# Sheet-NODE-V1_0.net
KiCad netlist of a schematic drawn in Altium Designer
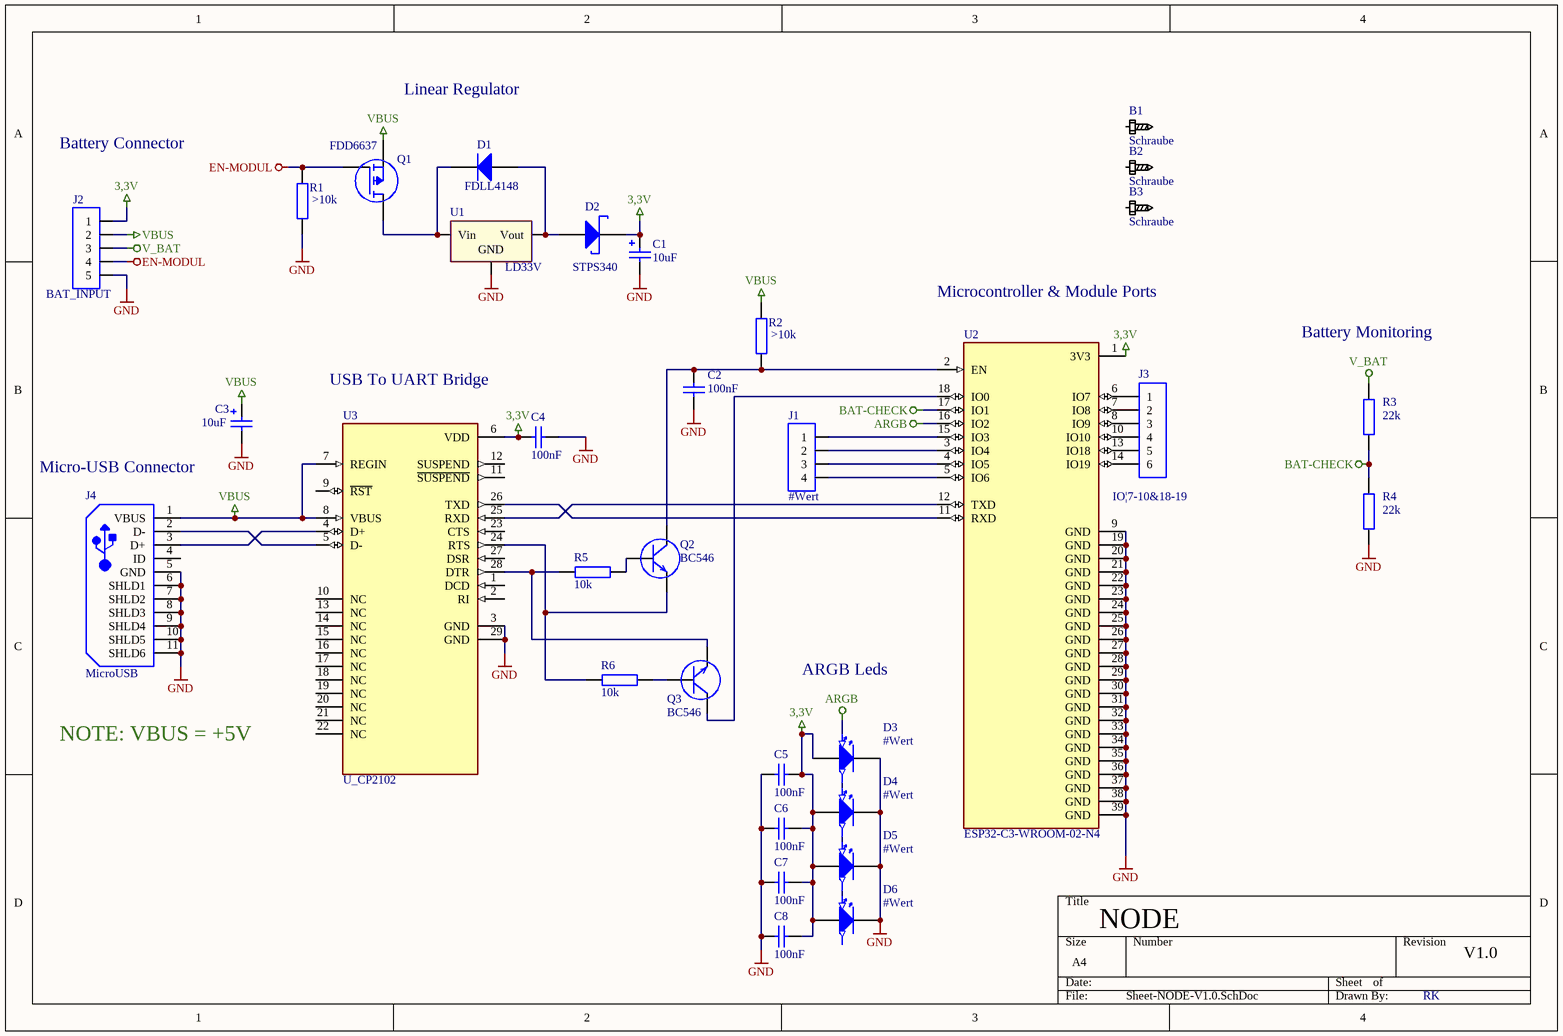
[diagram p0: Sheet-NODE-V1.0.SchDoc]

(export (version "E")
  (design (tool "Eeschema 10.0.6"))
  (components
    (comp (ref "B1")
      (value "Schraube")
      (footprint "B_Schraube-M3 PAD")
      (description "Schraubenloch für M3 Schrauben")
      (libsource (lib "SCHLIB-PCSB_5.1.3") (part "B_Schraube"))
    )
    (comp (ref "B2")
      (value "Schraube")
      (footprint "B_Schraube-M3 PAD")
      (description "Schraubenloch für M3 Schrauben")
      (libsource (lib "SCHLIB-PCSB_5.1.3") (part "B_Schraube"))
    )
    (comp (ref "B3")
      (value "Schraube")
      (footprint "B_Schraube-M3 PAD")
      (description "Schraubenloch für M3 Schrauben")
      (libsource (lib "SCHLIB-PCSB_5.1.3") (part "B_Schraube"))
    )
    (comp (ref "C1")
      (value "10uF")
      (footprint "C_SMD_B-Typ")
      (description "SMD Elektrolytkondensator")
      (libsource (lib "SCHLIB-PCSB_5.1.3") (part "C_SMD_ELK"))
    )
    (comp (ref "C2")
      (value "100nF")
      (footprint "C_SMD_0603")
      (description "Kondensator SMD Universal, Keramik, Folie, usw.")
      (libsource (lib "SCHLIB-PCSB_5.1.3") (part "C_SMD_KO"))
    )
    (comp (ref "C3")
      (value "10uF")
      (footprint "C_SMD_B-Typ")
      (description "SMD Elektrolytkondensator")
      (libsource (lib "SCHLIB-PCSB_5.1.3") (part "C_SMD_ELK"))
    )
    (comp (ref "C4")
      (value "100nF")
      (footprint "C_SMD_0603")
      (description "Kondensator SMD Universal, Keramik, Folie, usw.")
      (libsource (lib "SCHLIB-PCSB_5.1.3") (part "C_SMD_KO"))
    )
    (comp (ref "C5")
      (value "100nF")
      (footprint "C_SMD_0603")
      (description "Kondensator SMD Universal, Keramik, Folie, usw.")
      (libsource (lib "SCHLIB-PCSB_5.1.3") (part "C_SMD_KO"))
    )
    (comp (ref "C6")
      (value "100nF")
      (footprint "C_SMD_0603")
      (description "Kondensator SMD Universal, Keramik, Folie, usw.")
      (libsource (lib "SCHLIB-PCSB_5.1.3") (part "C_SMD_KO"))
    )
    (comp (ref "C7")
      (value "100nF")
      (footprint "C_SMD_0603")
      (description "Kondensator SMD Universal, Keramik, Folie, usw.")
      (libsource (lib "SCHLIB-PCSB_5.1.3") (part "C_SMD_KO"))
    )
    (comp (ref "C8")
      (value "100nF")
      (footprint "C_SMD_0603")
      (description "Kondensator SMD Universal, Keramik, Folie, usw.")
      (libsource (lib "SCHLIB-PCSB_5.1.3") (part "C_SMD_KO"))
    )
    (comp (ref "D1")
      (value "FDLL4148")
      (footprint "SOD-80-2")
      (description "Diode SMD Silizium")
      (libsource (lib "SCHLIB-PCSB_5.1.3") (part "D_SMD_Silizium"))
    )
    (comp (ref "D2")
      (value "STPS340")
      (footprint "D_DO-214")
      (description "Diode SMD Schottky")
      (libsource (lib "SCHLIB-PCSB_5.1.3") (part "D_SMD_Schottky"))
    )
    (comp (ref "D3")
      (value "#Wert")
      (footprint "D_SMD_LED-ARGB")
      (description "Diode SMD ARGB")
      (libsource (lib "SCHLIB-PCSB_5.1.3") (part "D_SMD_LED-ARGB"))
    )
    (comp (ref "D4")
      (value "#Wert")
      (footprint "D_SMD_LED-ARGB")
      (description "Diode SMD ARGB")
      (libsource (lib "SCHLIB-PCSB_5.1.3") (part "D_SMD_LED-ARGB"))
    )
    (comp (ref "D5")
      (value "#Wert")
      (footprint "D_SMD_LED-ARGB")
      (description "Diode SMD ARGB")
      (libsource (lib "SCHLIB-PCSB_5.1.3") (part "D_SMD_LED-ARGB"))
    )
    (comp (ref "D6")
      (value "#Wert")
      (footprint "D_SMD_LED-ARGB")
      (description "Diode SMD ARGB")
      (libsource (lib "SCHLIB-PCSB_5.1.3") (part "D_SMD_LED-ARGB"))
    )
    (comp (ref "J1")
      (value "#Wert")
      (footprint "Sip-4")
      (description "Stecker")
      (libsource (lib "SCHLIB-PCSB_5.1.3") (part "J_THT_CON4"))
    )
    (comp (ref "J2")
      (value "BAT_INPUT")
      (footprint "SIP-5")
      (description "Stecker")
      (libsource (lib "SCHLIB-PCSB_5.1.3") (part "J_THT_CON5"))
    )
    (comp (ref "J3")
      (value "IO¦7-10&18-19")
      (footprint "SIP-6")
      (description "Stecker")
      (libsource (lib "SCHLIB-PCSB_5.1.3") (part "J_THT_CON6"))
    )
    (comp (ref "J4")
      (value "MicroUSB")
      (footprint "J-SMD-Micro-USB")
      (description "Micro USB Buchse")
      (libsource (lib "SCHLIB-PCSB_5.1.3") (part "J_SMD_µ-USB"))
    )
    (comp (ref "Q1")
      (value "FDD6637")
      (footprint "FDD6637_TO-252-3")
      (description "P-Kanal MOSFET")
      (fields (field (name "MP") "IRFZ44NPBF") (field (name "DIGI-KEY_PART_NUMBER") "IRFZ44NPBF-ND"))
      (libsource (lib "SCHLIB-PCSB_5.1.3") (part "Q_SMD_MOSFET-P-Kanal"))
    )
    (comp (ref "Q2")
      (value "BC546")
      (footprint "TO-92-3")
      (description "NPN Transistor")
      (libsource (lib "SCHLIB-PCSB_5.1.3") (part "Q_SMD_NPN"))
    )
    (comp (ref "Q3")
      (value "BC546")
      (footprint "TO-92-3")
      (description "NPN Transistor")
      (libsource (lib "SCHLIB-PCSB_5.1.3") (part "Q_SMD_NPN"))
    )
    (comp (ref "R1")
      (value ">10k")
      (footprint "R_SMD_0805")
      (description "Widerstand SMD")
      (libsource (lib "SCHLIB-PCSB_5.1.3") (part "R_SMD_Widerstand"))
    )
    (comp (ref "R2")
      (value ">10k")
      (footprint "R_SMD_0805")
      (description "Widerstand SMD")
      (libsource (lib "SCHLIB-PCSB_5.1.3") (part "R_SMD_Widerstand"))
    )
    (comp (ref "R3")
      (value "22k")
      (footprint "R_SMD_0805")
      (description "Widerstand SMD")
      (libsource (lib "SCHLIB-PCSB_5.1.3") (part "R_SMD_Widerstand"))
    )
    (comp (ref "R4")
      (value "22k")
      (footprint "R_SMD_0805")
      (description "Widerstand SMD")
      (libsource (lib "SCHLIB-PCSB_5.1.3") (part "R_SMD_Widerstand"))
    )
    (comp (ref "R5")
      (value "10k")
      (footprint "R_SMD_0805")
      (description "Widerstand SMD")
      (libsource (lib "SCHLIB-PCSB_5.1.3") (part "R_SMD_Widerstand"))
    )
    (comp (ref "R6")
      (value "10k")
      (footprint "R_SMD_0805")
      (description "Widerstand SMD")
      (libsource (lib "SCHLIB-PCSB_5.1.3") (part "R_SMD_Widerstand"))
    )
    (comp (ref "U1")
      (value "LD33V")
      (footprint "TO-220-3V")
      (description "Linearwandler")
      (libsource (lib "SCHLIB-PCSB_5.1.3") (part "U_THT_78xx"))
    )
    (comp (ref "U2")
      (value "ESP32-C3-WROOM-02-N4")
      (footprint "MODULE_ESP32-C3-WROOM-02-H4")
      (fields (field (name "MF") "Espressif Systems"))
      (libsource (lib "SCHLIB-PCSB_5.1.3") (part "ESP32-C3-WROOM-02-N4"))
    )
    (comp (ref "U3")
      (value "U_CP2102")
      (footprint "QFN50P500X500X100-29N")
      (description "CP2102N USB 2.0 to UART (RS232) Bridge Interface Evaluation Board")
      (fields (field (name "MF") "Silicon Labs") (field (name "MP") "CP2102"))
      (libsource (lib "SCHLIB-PCSB_5.1.3") (part "U_CP2102"))
    )
  )
  (nets
    (net (code "1") (name "3,3V") (class "Default")
      (node (ref "C1") (pin "1") (pinfunction "1_1") (pintype "passive"))
      (node (ref "C4") (pin "1") (pintype "passive"))
      (node (ref "C5") (pin "2") (pintype "passive"))
      (node (ref "C6") (pin "2") (pintype "passive"))
      (node (ref "C7") (pin "2") (pintype "passive"))
      (node (ref "C8") (pin "2") (pintype "passive"))
      (node (ref "D2") (pin "2") (pinfunction "K_2") (pintype "passive"))
      (node (ref "D3") (pin "1") (pinfunction "VDD_1") (pintype "passive"))
      (node (ref "D4") (pin "1") (pinfunction "VDD_1") (pintype "passive"))
      (node (ref "D5") (pin "1") (pinfunction "VDD_1") (pintype "passive"))
      (node (ref "D6") (pin "1") (pinfunction "VDD_1") (pintype "passive"))
      (node (ref "J2") (pin "1") (pinfunction "1_1") (pintype "passive"))
      (node (ref "U2") (pin "1") (pinfunction "3V3_1") (pintype "power_in"))
      (node (ref "U3") (pin "6") (pinfunction "VDD_6") (pintype "power_in"))
    )
    (net (code "2") (name "ARGB") (class "Default")
      (node (ref "D3") (pin "4") (pinfunction "DIN_4") (pintype "input"))
      (node (ref "U2") (pin "16") (pinfunction "IO2_16") (pintype "bidirectional"))
    )
    (net (code "3") (name "BAT-CHECK") (class "Default")
      (node (ref "R3") (pin "1") (pintype "passive"))
      (node (ref "R4") (pin "2") (pintype "passive"))
      (node (ref "U2") (pin "17") (pinfunction "IO1_17") (pintype "bidirectional"))
    )
    (net (code "4") (name "EN-MODUL") (class "Default")
      (node (ref "J2") (pin "4") (pinfunction "4_4") (pintype "passive"))
      (node (ref "Q1") (pin "G") (pinfunction "G_G") (pintype "passive"))
      (node (ref "R1") (pin "2") (pintype "passive"))
    )
    (net (code "5") (name "GND") (class "Default")
      (node (ref "C1") (pin "2") (pinfunction "2_2") (pintype "passive"))
      (node (ref "C2") (pin "1") (pintype "passive"))
      (node (ref "C3") (pin "2") (pinfunction "2_2") (pintype "passive"))
      (node (ref "C4") (pin "2") (pintype "passive"))
      (node (ref "C5") (pin "1") (pintype "passive"))
      (node (ref "C6") (pin "1") (pintype "passive"))
      (node (ref "C7") (pin "1") (pintype "passive"))
      (node (ref "C8") (pin "1") (pintype "passive"))
      (node (ref "D3") (pin "3") (pinfunction "GND_3") (pintype "passive"))
      (node (ref "D4") (pin "3") (pinfunction "GND_3") (pintype "passive"))
      (node (ref "D5") (pin "3") (pinfunction "GND_3") (pintype "passive"))
      (node (ref "D6") (pin "3") (pinfunction "GND_3") (pintype "passive"))
      (node (ref "J2") (pin "5") (pinfunction "5_5") (pintype "passive"))
      (node (ref "J4") (pin "10") (pinfunction "SHLD5_10") (pintype "passive"))
      (node (ref "J4") (pin "11") (pinfunction "SHLD6_11") (pintype "passive"))
      (node (ref "J4") (pin "5") (pinfunction "GND_5") (pintype "passive"))
      (node (ref "J4") (pin "6") (pinfunction "SHLD1_6") (pintype "passive"))
      (node (ref "J4") (pin "7") (pinfunction "SHLD2_7") (pintype "passive"))
      (node (ref "J4") (pin "8") (pinfunction "SHLD3_8") (pintype "passive"))
      (node (ref "J4") (pin "9") (pinfunction "SHLD4_9") (pintype "passive"))
      (node (ref "R1") (pin "1") (pintype "passive"))
      (node (ref "R4") (pin "1") (pintype "passive"))
      (node (ref "U1") (pin "3") (pinfunction "GND_3") (pintype "passive"))
      (node (ref "U2") (pin "19") (pinfunction "GND_19") (pintype "power_in"))
      (node (ref "U2") (pin "20") (pinfunction "GND_20") (pintype "power_in"))
      (node (ref "U2") (pin "21") (pinfunction "GND_21") (pintype "power_in"))
      (node (ref "U2") (pin "22") (pinfunction "GND_22") (pintype "power_in"))
      (node (ref "U2") (pin "23") (pinfunction "GND_23") (pintype "power_in"))
      (node (ref "U2") (pin "24") (pinfunction "GND_24") (pintype "power_in"))
      (node (ref "U2") (pin "25") (pinfunction "GND_25") (pintype "power_in"))
      (node (ref "U2") (pin "26") (pinfunction "GND_26") (pintype "power_in"))
      (node (ref "U2") (pin "27") (pinfunction "GND_27") (pintype "power_in"))
      (node (ref "U2") (pin "28") (pinfunction "GND_28") (pintype "power_in"))
      (node (ref "U2") (pin "29") (pinfunction "GND_29") (pintype "power_in"))
      (node (ref "U2") (pin "30") (pinfunction "GND_30") (pintype "power_in"))
      (node (ref "U2") (pin "31") (pinfunction "GND_31") (pintype "power_in"))
      (node (ref "U2") (pin "32") (pinfunction "GND_32") (pintype "power_in"))
      (node (ref "U2") (pin "33") (pinfunction "GND_33") (pintype "power_in"))
      (node (ref "U2") (pin "34") (pinfunction "GND_34") (pintype "power_in"))
      (node (ref "U2") (pin "35") (pinfunction "GND_35") (pintype "power_in"))
      (node (ref "U2") (pin "36") (pinfunction "GND_36") (pintype "power_in"))
      (node (ref "U2") (pin "37") (pinfunction "GND_37") (pintype "power_in"))
      (node (ref "U2") (pin "38") (pinfunction "GND_38") (pintype "power_in"))
      (node (ref "U2") (pin "39") (pinfunction "GND_39") (pintype "power_in"))
      (node (ref "U2") (pin "9") (pinfunction "GND_9") (pintype "power_in"))
      (node (ref "U3") (pin "29") (pinfunction "GND_29") (pintype "power_in"))
      (node (ref "U3") (pin "3") (pinfunction "GND_3") (pintype "power_in"))
    )
    (net (code "6") (name "Net-(D1-A)") (class "Default")
      (node (ref "D1") (pin "1") (pinfunction "A_1") (pintype "passive"))
      (node (ref "D2") (pin "1") (pinfunction "A_1") (pintype "passive"))
      (node (ref "U1") (pin "2") (pinfunction "Vout_2") (pintype "passive"))
    )
    (net (code "7") (name "Net-(D1-K)") (class "Default")
      (node (ref "D1") (pin "2") (pinfunction "K_2") (pintype "passive"))
      (node (ref "Q1") (pin "D") (pinfunction "D_D") (pintype "passive"))
      (node (ref "U1") (pin "1") (pinfunction "Vin_1") (pintype "passive"))
    )
    (net (code "8") (name "Net-(D3-DOUT)") (class "Default")
      (node (ref "D3") (pin "2") (pinfunction "DOUT_2") (pintype "output"))
      (node (ref "D4") (pin "4") (pinfunction "DIN_4") (pintype "input"))
    )
    (net (code "9") (name "Net-(D4-DOUT)") (class "Default")
      (node (ref "D4") (pin "2") (pinfunction "DOUT_2") (pintype "output"))
      (node (ref "D5") (pin "4") (pinfunction "DIN_4") (pintype "input"))
    )
    (net (code "10") (name "Net-(D5-DOUT)") (class "Default")
      (node (ref "D5") (pin "2") (pinfunction "DOUT_2") (pintype "output"))
      (node (ref "D6") (pin "4") (pinfunction "DIN_4") (pintype "input"))
    )
    (net (code "11") (name "Net-(J4-D+)") (class "Default")
      (node (ref "J4") (pin "3") (pinfunction "D+_3") (pintype "passive"))
      (node (ref "U3") (pin "4") (pinfunction "D+_4") (pintype "bidirectional"))
    )
    (net (code "12") (name "Net-(J4-D-)") (class "Default")
      (node (ref "J4") (pin "2") (pinfunction "D-_2") (pintype "passive"))
      (node (ref "U3") (pin "5") (pinfunction "D-_5") (pintype "bidirectional"))
    )
    (net (code "13") (name "Net-(Q2-B)") (class "Default")
      (node (ref "Q2") (pin "1") (pinfunction "B_1") (pintype "passive"))
      (node (ref "R5") (pin "2") (pintype "passive"))
    )
    (net (code "14") (name "Net-(Q2-C)") (class "Default")
      (node (ref "C2") (pin "2") (pintype "passive"))
      (node (ref "Q2") (pin "3") (pinfunction "C_3") (pintype "passive"))
      (node (ref "R2") (pin "1") (pintype "passive"))
      (node (ref "U2") (pin "2") (pinfunction "EN_2") (pintype "input"))
    )
    (net (code "15") (name "Net-(Q2-E)") (class "Default")
      (node (ref "Q2") (pin "2") (pinfunction "E_2") (pintype "passive"))
      (node (ref "R6") (pin "1") (pintype "passive"))
      (node (ref "U3") (pin "24") (pinfunction "RTS_24") (pintype "output"))
    )
    (net (code "16") (name "Net-(Q3-B)") (class "Default")
      (node (ref "Q3") (pin "1") (pinfunction "B_1") (pintype "passive"))
      (node (ref "R6") (pin "2") (pintype "passive"))
    )
    (net (code "17") (name "Net-(Q3-C)") (class "Default")
      (node (ref "Q3") (pin "3") (pinfunction "C_3") (pintype "passive"))
      (node (ref "U2") (pin "18") (pinfunction "IO0_18") (pintype "bidirectional"))
    )
    (net (code "18") (name "Net-(Q3-E)") (class "Default")
      (node (ref "Q3") (pin "2") (pinfunction "E_2") (pintype "passive"))
      (node (ref "R5") (pin "1") (pintype "passive"))
      (node (ref "U3") (pin "28") (pinfunction "DTR_28") (pintype "output"))
    )
    (net (code "19") (name "Net-(U2-IO3)") (class "Default")
      (node (ref "J1") (pin "1") (pinfunction "1_1") (pintype "passive"))
      (node (ref "U2") (pin "15") (pinfunction "IO3_15") (pintype "bidirectional"))
    )
    (net (code "20") (name "Net-(U2-IO4)") (class "Default")
      (node (ref "J1") (pin "2") (pinfunction "2_2") (pintype "passive"))
      (node (ref "U2") (pin "3") (pinfunction "IO4_3") (pintype "bidirectional"))
    )
    (net (code "21") (name "Net-(U2-IO5)") (class "Default")
      (node (ref "J1") (pin "3") (pinfunction "3_3") (pintype "passive"))
      (node (ref "U2") (pin "4") (pinfunction "IO5_4") (pintype "bidirectional"))
    )
    (net (code "22") (name "Net-(U2-IO6)") (class "Default")
      (node (ref "J1") (pin "4") (pinfunction "4_4") (pintype "passive"))
      (node (ref "U2") (pin "5") (pinfunction "IO6_5") (pintype "bidirectional"))
    )
    (net (code "23") (name "Net-(U2-IO7)") (class "Default")
      (node (ref "J3") (pin "1") (pinfunction "1_1") (pintype "passive"))
      (node (ref "U2") (pin "6") (pinfunction "IO7_6") (pintype "bidirectional"))
    )
    (net (code "24") (name "Net-(U2-IO8)") (class "Default")
      (node (ref "J3") (pin "2") (pinfunction "2_2") (pintype "passive"))
      (node (ref "U2") (pin "7") (pinfunction "IO8_7") (pintype "bidirectional"))
    )
    (net (code "25") (name "Net-(U2-IO9)") (class "Default")
      (node (ref "J3") (pin "3") (pinfunction "3_3") (pintype "passive"))
      (node (ref "U2") (pin "8") (pinfunction "IO9_8") (pintype "bidirectional"))
    )
    (net (code "26") (name "Net-(U2-IO10)") (class "Default")
      (node (ref "J3") (pin "4") (pinfunction "4_4") (pintype "passive"))
      (node (ref "U2") (pin "10") (pinfunction "IO10_10") (pintype "bidirectional"))
    )
    (net (code "27") (name "Net-(U2-IO18)") (class "Default")
      (node (ref "J3") (pin "5") (pinfunction "5_5") (pintype "passive"))
      (node (ref "U2") (pin "13") (pinfunction "IO18_13") (pintype "bidirectional"))
    )
    (net (code "28") (name "Net-(U2-IO19)") (class "Default")
      (node (ref "J3") (pin "6") (pinfunction "6_6") (pintype "passive"))
      (node (ref "U2") (pin "14") (pinfunction "IO19_14") (pintype "bidirectional"))
    )
    (net (code "29") (name "Net-(U2-RXD)") (class "Default")
      (node (ref "U2") (pin "11") (pinfunction "RXD_11") (pintype "bidirectional"))
      (node (ref "U3") (pin "26") (pinfunction "TXD_26") (pintype "output"))
    )
    (net (code "30") (name "Net-(U2-TXD)") (class "Default")
      (node (ref "U2") (pin "12") (pinfunction "TXD_12") (pintype "bidirectional"))
      (node (ref "U3") (pin "25") (pinfunction "RXD_25") (pintype "input"))
    )
    (net (code "31") (name "VBUS") (class "Default")
      (node (ref "C3") (pin "1") (pinfunction "1_1") (pintype "passive"))
      (node (ref "J2") (pin "2") (pinfunction "2_2") (pintype "passive"))
      (node (ref "J4") (pin "1") (pinfunction "VBUS_1") (pintype "passive"))
      (node (ref "Q1") (pin "S") (pinfunction "S_S") (pintype "passive"))
      (node (ref "R2") (pin "2") (pintype "passive"))
      (node (ref "U3") (pin "7") (pinfunction "REGIN_7") (pintype "input"))
      (node (ref "U3") (pin "8") (pinfunction "VBUS_8") (pintype "input"))
    )
    (net (code "32") (name "V_BAT") (class "Default")
      (node (ref "J2") (pin "3") (pinfunction "3_3") (pintype "passive"))
      (node (ref "R3") (pin "2") (pintype "passive"))
    )
    (net (code "33") (name "unconnected-(B1-PAD-Pad1)") (class "Default")
      (node (ref "B1") (pin "1") (pinfunction "PAD_1") (pintype "passive"))
    )
    (net (code "34") (name "unconnected-(B2-PAD-Pad1)") (class "Default")
      (node (ref "B2") (pin "1") (pinfunction "PAD_1") (pintype "passive"))
    )
    (net (code "35") (name "unconnected-(B3-PAD-Pad1)") (class "Default")
      (node (ref "B3") (pin "1") (pinfunction "PAD_1") (pintype "passive"))
    )
    (net (code "36") (name "unconnected-(D6-DOUT-Pad2)") (class "Default")
      (node (ref "D6") (pin "2") (pinfunction "DOUT_2") (pintype "output"))
    )
    (net (code "37") (name "unconnected-(J4-ID-Pad4)") (class "Default")
      (node (ref "J4") (pin "4") (pinfunction "ID_4") (pintype "passive"))
    )
    (net (code "38") (name "unconnected-(U3-CTS-Pad23)") (class "Default")
      (node (ref "U3") (pin "23") (pinfunction "CTS_23") (pintype "input"))
    )
    (net (code "39") (name "unconnected-(U3-DCD-Pad1)") (class "Default")
      (node (ref "U3") (pin "1") (pinfunction "DCD_1") (pintype "input"))
    )
    (net (code "40") (name "unconnected-(U3-DSR-Pad27)") (class "Default")
      (node (ref "U3") (pin "27") (pinfunction "DSR_27") (pintype "input"))
    )
    (net (code "41") (name "unconnected-(U3-NC-Pad10)") (class "Default")
      (node (ref "U3") (pin "10") (pinfunction "NC_10") (pintype "passive"))
    )
    (net (code "42") (name "unconnected-(U3-NC-Pad13)") (class "Default")
      (node (ref "U3") (pin "13") (pinfunction "NC_13") (pintype "passive"))
    )
    (net (code "43") (name "unconnected-(U3-NC-Pad14)") (class "Default")
      (node (ref "U3") (pin "14") (pinfunction "NC_14") (pintype "passive"))
    )
    (net (code "44") (name "unconnected-(U3-NC-Pad15)") (class "Default")
      (node (ref "U3") (pin "15") (pinfunction "NC_15") (pintype "passive"))
    )
    (net (code "45") (name "unconnected-(U3-NC-Pad16)") (class "Default")
      (node (ref "U3") (pin "16") (pinfunction "NC_16") (pintype "passive"))
    )
    (net (code "46") (name "unconnected-(U3-NC-Pad17)") (class "Default")
      (node (ref "U3") (pin "17") (pinfunction "NC_17") (pintype "passive"))
    )
    (net (code "47") (name "unconnected-(U3-NC-Pad18)") (class "Default")
      (node (ref "U3") (pin "18") (pinfunction "NC_18") (pintype "passive"))
    )
    (net (code "48") (name "unconnected-(U3-NC-Pad19)") (class "Default")
      (node (ref "U3") (pin "19") (pinfunction "NC_19") (pintype "passive"))
    )
    (net (code "49") (name "unconnected-(U3-NC-Pad20)") (class "Default")
      (node (ref "U3") (pin "20") (pinfunction "NC_20") (pintype "passive"))
    )
    (net (code "50") (name "unconnected-(U3-NC-Pad21)") (class "Default")
      (node (ref "U3") (pin "21") (pinfunction "NC_21") (pintype "passive"))
    )
    (net (code "51") (name "unconnected-(U3-NC-Pad22)") (class "Default")
      (node (ref "U3") (pin "22") (pinfunction "NC_22") (pintype "passive"))
    )
    (net (code "52") (name "unconnected-(U3-RI-Pad2)") (class "Default")
      (node (ref "U3") (pin "2") (pinfunction "RI_2") (pintype "input"))
    )
    (net (code "53") (name "unconnected-(U3-SUSPEND-Pad12)") (class "Default")
      (node (ref "U3") (pin "12") (pinfunction "SUSPEND_12") (pintype "output"))
    )
    (net (code "54") (name "unconnected-(U3-~{RST}-Pad9)") (class "Default")
      (node (ref "U3") (pin "9") (pinfunction "~{RST}_9") (pintype "bidirectional"))
    )
    (net (code "55") (name "unconnected-(U3-~{SUSPEND}-Pad11)") (class "Default")
      (node (ref "U3") (pin "11") (pinfunction "~{SUSPEND}_11") (pintype "output"))
    )
  )
)
